# USB_OTG.net
KiCad netlist of a schematic drawn in Altium Designer
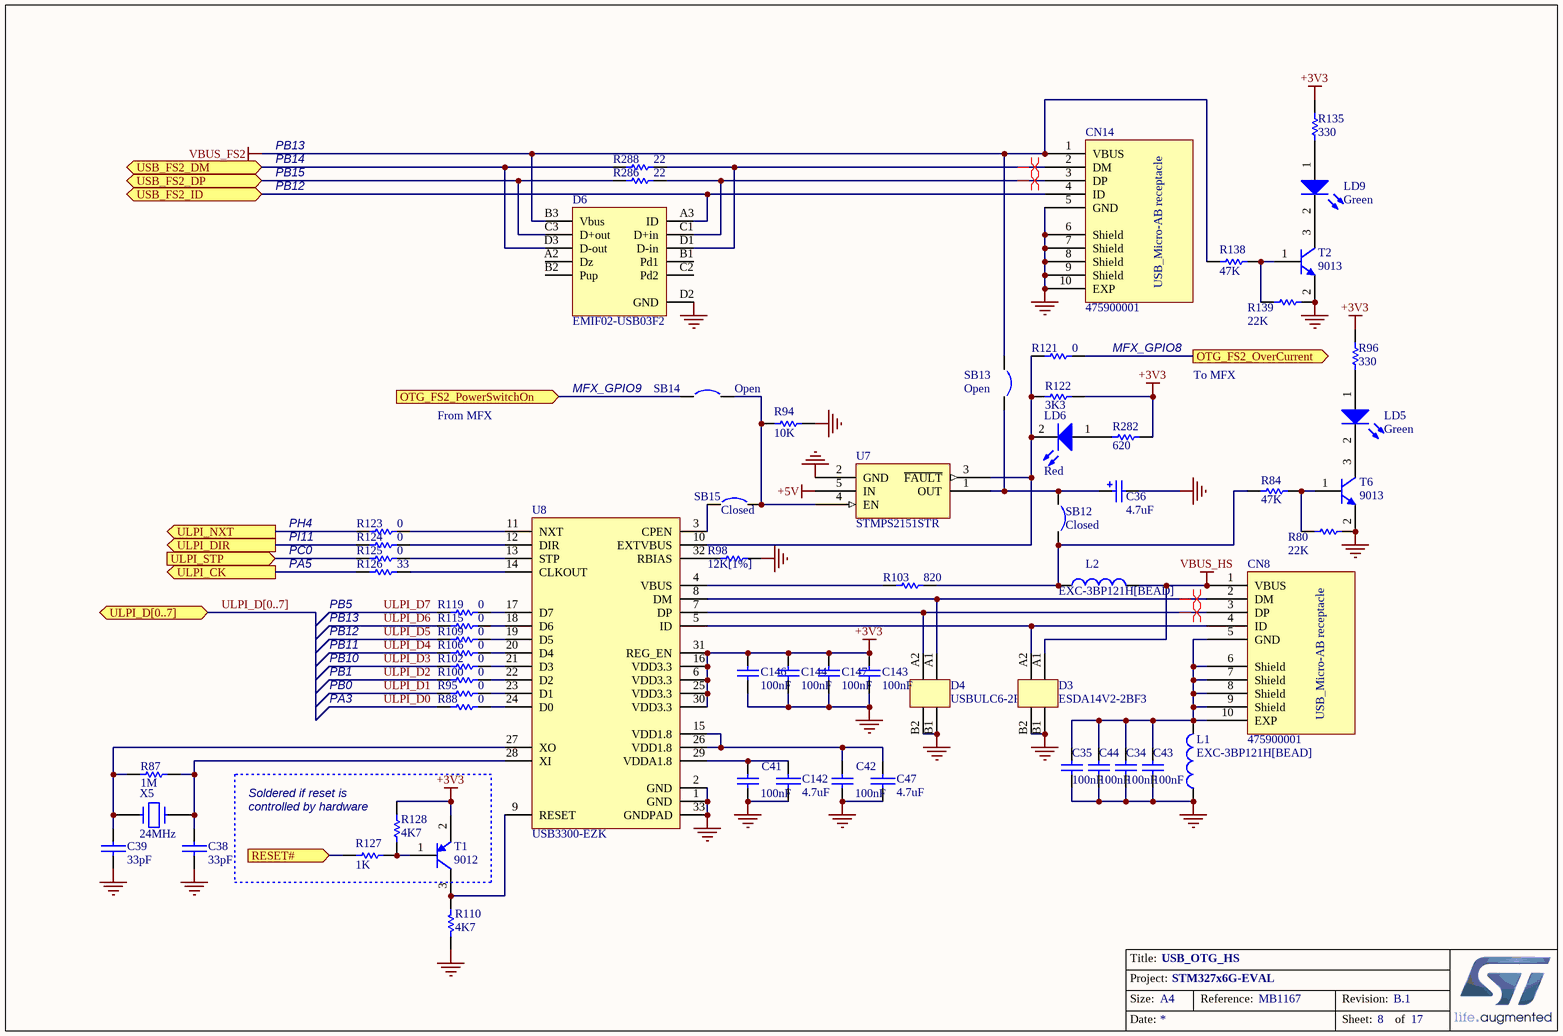
[diagram p0: USB_OTG.SchDoc]

(export (version "E")
  (design (tool "Eeschema 10.0.6"))
  (components
    (comp (ref "C34")
      (value "100nF")
      (footprint "0603C")
      (description "Capacitor")
      (fields (field (name "PUBLISHER") "Altium Limited"))
      (libsource (lib "Miscellaneous Devices") (part "Cap"))
    )
    (comp (ref "C35")
      (value "100nF")
      (footprint "0603C")
      (description "Capacitor")
      (fields (field (name "PUBLISHER") "Altium Limited"))
      (libsource (lib "Miscellaneous Devices") (part "Cap"))
    )
    (comp (ref "C36")
      (value "4.7uF")
      (footprint "TAN-A")
      (description "Polarized Capacitor (Radial)")
      (fields (field (name "PUBLISHER") "Altium Limited"))
      (libsource (lib "Miscellaneous Devices") (part "Cap Pol1"))
    )
    (comp (ref "C38")
      (value "33pF")
      (footprint "0603C")
      (description "Capacitor")
      (libsource (lib "") (part "CAP_1"))
    )
    (comp (ref "C39")
      (value "33pF")
      (footprint "0603C")
      (description "Capacitor")
      (libsource (lib "") (part "CAP_1"))
    )
    (comp (ref "C41")
      (value "100nF")
      (footprint "0603C")
      (description "Capacitor")
      (fields (field (name "PUBLISHER") "Altium Limited"))
      (libsource (lib "Miscellaneous Devices") (part "Cap"))
    )
    (comp (ref "C42")
      (value "100nF")
      (footprint "0603C")
      (description "Capacitor")
      (fields (field (name "PUBLISHER") "Altium Limited"))
      (libsource (lib "Miscellaneous Devices") (part "Cap"))
    )
    (comp (ref "C43")
      (value "100nF")
      (footprint "0603C")
      (description "Capacitor")
      (fields (field (name "PUBLISHER") "Altium Limited"))
      (libsource (lib "Miscellaneous Devices") (part "Cap"))
    )
    (comp (ref "C44")
      (value "100nF")
      (footprint "0603C")
      (description "Capacitor")
      (fields (field (name "PUBLISHER") "Altium Limited"))
      (libsource (lib "Miscellaneous Devices") (part "Cap"))
    )
    (comp (ref "C47")
      (value "4.7uF")
      (footprint "TAN-A")
      (description "Capacitor")
      (libsource (lib "*") (part "CAP"))
    )
    (comp (ref "C142")
      (value "4.7uF")
      (footprint "TAN-A")
      (description "Capacitor")
      (libsource (lib "*") (part "CAP"))
    )
    (comp (ref "C143")
      (value "100nF")
      (footprint "0603C")
      (description "Capacitor")
      (fields (field (name "PUBLISHER") "Altium Limited"))
      (libsource (lib "Miscellaneous Devices") (part "Cap"))
    )
    (comp (ref "C144")
      (value "100nF")
      (footprint "0603C")
      (description "Capacitor")
      (fields (field (name "PUBLISHER") "Altium Limited"))
      (libsource (lib "Miscellaneous Devices") (part "Cap"))
    )
    (comp (ref "C146")
      (value "100nF")
      (footprint "0603C")
      (description "Capacitor")
      (fields (field (name "PUBLISHER") "Altium Limited"))
      (libsource (lib "Miscellaneous Devices") (part "Cap"))
    )
    (comp (ref "C147")
      (value "100nF")
      (footprint "0603C")
      (description "Capacitor")
      (fields (field (name "PUBLISHER") "Altium Limited"))
      (libsource (lib "Miscellaneous Devices") (part "Cap"))
    )
    (comp (ref "CN8")
      (value "475900001")
      (footprint "MOLEX_47590001")
      (libsource (lib "mb1045") (part "475900001"))
    )
    (comp (ref "CN14")
      (value "475900001")
      (footprint "MOLEX_47590001")
      (libsource (lib "mb1045") (part "475900001"))
    )
    (comp (ref "D3")
      (value "ESDA14V2-2BF3")
      (footprint "BGA4_0R4_0R8X0R8")
      (libsource (lib "MB786") (part "ESDA14V2-2BF3"))
    )
    (comp (ref "D4")
      (value "USBULC6-2F3")
      (footprint "BGA4_0R4_1X1")
      (libsource (lib "MB786") (part "USBULC6-2F3"))
    )
    (comp (ref "D6")
      (value "EMIF02-USB03F2")
      (footprint "BGA11_0R5_1R57X2R07")
      (libsource (lib "mb1045") (part "EMIF02-USB03F2"))
    )
    (comp (ref "L1")
      (value "EXC-3BP121H[BEAD]")
      (footprint "0603L")
      (description "Inductor")
      (fields (field (name "PUBLISHER") "Altium Limited"))
      (libsource (lib "Miscellaneous Devices") (part "Inductor"))
    )
    (comp (ref "L2")
      (value "EXC-3BP121H[BEAD]")
      (footprint "0603L")
      (description "Inductor")
      (fields (field (name "PUBLISHER") "Altium Limited"))
      (libsource (lib "Miscellaneous Devices") (part "Inductor"))
    )
    (comp (ref "LD5")
      (value "Green")
      (footprint "0603D")
      (description "Typical RED, GREEN, YELLOW, AMBER GaAs LED")
      (fields (field (name "PUBLISHER") "Altium Limited"))
      (libsource (lib "Miscellaneous Devices") (part "LED2"))
    )
    (comp (ref "LD6")
      (value "Red")
      (footprint "0603D")
      (description "Typical RED, GREEN, YELLOW, AMBER GaAs LED")
      (fields (field (name "PUBLISHER") "Altium Limited"))
      (libsource (lib "Miscellaneous Devices") (part "LED2"))
    )
    (comp (ref "LD9")
      (value "Green")
      (footprint "0603D")
      (description "Typical RED, GREEN, YELLOW, AMBER GaAs LED")
      (fields (field (name "PUBLISHER") "Altium Limited"))
      (libsource (lib "Miscellaneous Devices") (part "LED2"))
    )
    (comp (ref "R80")
      (value "22K")
      (footprint "0603R")
      (description "Resistor")
      (fields (field (name "PUBLISHER") "Altium Limited"))
      (libsource (lib "Miscellaneous Devices") (part "res1"))
    )
    (comp (ref "R84")
      (value "47K")
      (footprint "0603R")
      (description "Resistor")
      (fields (field (name "PUBLISHER") "Altium Limited"))
      (libsource (lib "Miscellaneous Devices") (part "res1"))
    )
    (comp (ref "R87")
      (value "1M")
      (footprint "0603R")
      (description "Resistor")
      (fields (field (name "PUBLISHER") "Altium Limited"))
      (libsource (lib "Miscellaneous Devices") (part "Res1"))
    )
    (comp (ref "R88")
      (value "0")
      (footprint "0603R")
      (description "Resistor")
      (fields (field (name "PUBLISHER") "Altium Limited"))
      (libsource (lib "Miscellaneous Devices") (part "Res1"))
    )
    (comp (ref "R94")
      (value "10K")
      (footprint "0603R")
      (description "Resistor")
      (fields (field (name "PUBLISHER") "Altium Limited"))
      (libsource (lib "Miscellaneous Devices") (part "res1"))
    )
    (comp (ref "R95")
      (value "0")
      (footprint "0603R")
      (description "Resistor")
      (fields (field (name "PUBLISHER") "Altium Limited"))
      (libsource (lib "Miscellaneous Devices") (part "Res1"))
    )
    (comp (ref "R96")
      (value "330")
      (footprint "0603R")
      (description "Resistor")
      (fields (field (name "PUBLISHER") "Altium Limited"))
      (libsource (lib "Miscellaneous Devices") (part "res1"))
    )
    (comp (ref "R98")
      (value "12K[1%]")
      (footprint "0603R")
      (description "Resistor")
      (fields (field (name "PUBLISHER") "Altium Limited"))
      (libsource (lib "Miscellaneous Devices") (part "Res1"))
    )
    (comp (ref "R100")
      (value "0")
      (footprint "0603R")
      (description "Resistor")
      (fields (field (name "PUBLISHER") "Altium Limited"))
      (libsource (lib "Miscellaneous Devices") (part "Res1"))
    )
    (comp (ref "R102")
      (value "0")
      (footprint "0603R")
      (description "Resistor")
      (fields (field (name "PUBLISHER") "Altium Limited"))
      (libsource (lib "Miscellaneous Devices") (part "Res1"))
    )
    (comp (ref "R103")
      (value "820")
      (footprint "0603R")
      (description "Resistor")
      (fields (field (name "PUBLISHER") "Altium Limited"))
      (libsource (lib "Miscellaneous Devices") (part "res1"))
    )
    (comp (ref "R106")
      (value "0")
      (footprint "0603R")
      (description "Resistor")
      (fields (field (name "PUBLISHER") "Altium Limited"))
      (libsource (lib "Miscellaneous Devices") (part "Res1"))
    )
    (comp (ref "R109")
      (value "0")
      (footprint "0603R")
      (description "Resistor")
      (fields (field (name "PUBLISHER") "Altium Limited"))
      (libsource (lib "Miscellaneous Devices") (part "Res1"))
    )
    (comp (ref "R110")
      (value "4K7")
      (footprint "0603R")
      (description "Resistor")
      (fields (field (name "PUBLISHER") "Altium Limited"))
      (libsource (lib "*") (part "Res1"))
    )
    (comp (ref "R115")
      (value "0")
      (footprint "0603R")
      (description "Resistor")
      (fields (field (name "PUBLISHER") "Altium Limited"))
      (libsource (lib "Miscellaneous Devices") (part "Res1"))
    )
    (comp (ref "R119")
      (value "0")
      (footprint "0603R")
      (description "Resistor")
      (fields (field (name "PUBLISHER") "Altium Limited"))
      (libsource (lib "Miscellaneous Devices") (part "Res1"))
    )
    (comp (ref "R121")
      (value "0")
      (footprint "0603R")
      (description "Resistor")
      (fields (field (name "PUBLISHER") "Altium Limited"))
      (libsource (lib "Miscellaneous Devices") (part "Res1"))
    )
    (comp (ref "R122")
      (value "3K3")
      (footprint "0603R")
      (description "Resistor")
      (fields (field (name "PUBLISHER") "Altium Limited"))
      (libsource (lib "Miscellaneous Devices") (part "res1"))
    )
    (comp (ref "R123")
      (value "0")
      (footprint "0603R")
      (description "Resistor")
      (fields (field (name "PUBLISHER") "Altium Limited"))
      (libsource (lib "Miscellaneous Devices") (part "Res1"))
    )
    (comp (ref "R124")
      (value "0")
      (footprint "0603R")
      (description "Resistor")
      (fields (field (name "PUBLISHER") "Altium Limited"))
      (libsource (lib "Miscellaneous Devices") (part "Res1"))
    )
    (comp (ref "R125")
      (value "0")
      (footprint "0603R")
      (description "Resistor")
      (fields (field (name "PUBLISHER") "Altium Limited"))
      (libsource (lib "Miscellaneous Devices") (part "Res1"))
    )
    (comp (ref "R126")
      (value "33")
      (footprint "0603R")
      (description "Resistor")
      (fields (field (name "PUBLISHER") "Altium Limited"))
      (libsource (lib "Miscellaneous Devices") (part "Res1"))
    )
    (comp (ref "R127")
      (value "1K")
      (footprint "0603R")
      (description "Resistor")
      (fields (field (name "PUBLISHER") "Altium Limited"))
      (libsource (lib "Miscellaneous Devices") (part "Res1"))
    )
    (comp (ref "R128")
      (value "4K7")
      (footprint "0603R")
      (description "Resistor")
      (fields (field (name "PUBLISHER") "Altium Limited"))
      (libsource (lib "*") (part "Res1"))
    )
    (comp (ref "R135")
      (value "330")
      (footprint "0603R")
      (description "Resistor")
      (fields (field (name "PUBLISHER") "Altium Limited"))
      (libsource (lib "Miscellaneous Devices") (part "res1"))
    )
    (comp (ref "R138")
      (value "47K")
      (footprint "0603R")
      (description "Resistor")
      (fields (field (name "PUBLISHER") "Altium Limited"))
      (libsource (lib "Miscellaneous Devices") (part "res1"))
    )
    (comp (ref "R139")
      (value "22K")
      (footprint "0603R")
      (description "Resistor")
      (fields (field (name "PUBLISHER") "Altium Limited"))
      (libsource (lib "Miscellaneous Devices") (part "res1"))
    )
    (comp (ref "R282")
      (value "620")
      (footprint "0603R")
      (description "Resistor")
      (fields (field (name "PUBLISHER") "Altium Limited"))
      (libsource (lib "Miscellaneous Devices") (part "Res1"))
    )
    (comp (ref "R286")
      (value "22")
      (footprint "0603R")
      (description "Resistor")
      (fields (field (name "PUBLISHER") "Altium Limited"))
      (libsource (lib "Miscellaneous Devices") (part "Res1"))
    )
    (comp (ref "R288")
      (value "22")
      (footprint "0603R")
      (description "Resistor")
      (fields (field (name "PUBLISHER") "Altium Limited"))
      (libsource (lib "Miscellaneous Devices") (part "Res1"))
    )
    (comp (ref "SB12")
      (value "Closed")
      (footprint "SB_0603")
      (description "Circuit Breaker")
      (fields (field (name "PUBLISHER") "Altium Limited"))
      (libsource (lib "MB1167") (part "Circuit Breaker_close"))
    )
    (comp (ref "SB13")
      (value "Open")
      (footprint "SB_0603")
      (description "Circuit Breaker")
      (fields (field (name "PUBLISHER") "Altium Limited"))
      (libsource (lib "MB1167") (part "Circuit Breaker"))
    )
    (comp (ref "SB14")
      (value "Open")
      (footprint "SB_0603")
      (description "Circuit Breaker")
      (fields (field (name "PUBLISHER") "Altium Limited"))
      (libsource (lib "MB1167") (part "Circuit Breaker"))
    )
    (comp (ref "SB15")
      (value "Closed")
      (footprint "SB_0603")
      (description "Circuit Breaker")
      (fields (field (name "PUBLISHER") "Altium Limited"))
      (libsource (lib "MB1167") (part "Circuit Breaker_close"))
    )
    (comp (ref "T1")
      (value "9012")
      (footprint "SOT-23")
      (description "PNP Bipolar Transistor")
      (fields (field (name "PUBLISHER") "Altium Limited"))
      (libsource (lib "MB1167") (part "PNP"))
    )
    (comp (ref "T2")
      (value "9013")
      (footprint "SOT-23")
      (description "NPN Bipolar Transistor")
      (fields (field (name "PUBLISHER") "Altium Limited"))
      (libsource (lib "MB1167") (part "NPN"))
    )
    (comp (ref "T6")
      (value "9013")
      (footprint "SOT-23")
      (description "NPN Bipolar Transistor")
      (fields (field (name "PUBLISHER") "Altium Limited"))
      (libsource (lib "MB1167") (part "NPN"))
    )
    (comp (ref "U7")
      (value "STMPS2151STR")
      (footprint "SOT23-5")
      (libsource (lib "mb1045") (part "STMPS2141STR"))
    )
    (comp (ref "U8")
      (value "USB3300-EZK")
      (footprint "QFN32_0R5_5X5")
      (libsource (lib "MB1000_1") (part "USB3300-EZK"))
    )
    (comp (ref "X5")
      (value "24MHz")
      (footprint "XTAL1")
      (description "Crystal")
      (libsource (lib "*") (part "CRYSTAL"))
    )
  )
  (nets
    (net (code "1") (name "+3V3") (class "Default")
      (node (ref "C143") (pin "1") (pinfunction "1_1") (pintype "passive"))
      (node (ref "C144") (pin "1") (pinfunction "1_1") (pintype "passive"))
      (node (ref "C146") (pin "1") (pinfunction "1_1") (pintype "passive"))
      (node (ref "C147") (pin "1") (pinfunction "1_1") (pintype "passive"))
      (node (ref "R122") (pin "1") (pinfunction "1_1") (pintype "passive"))
      (node (ref "R128") (pin "1") (pinfunction "1_1") (pintype "passive"))
      (node (ref "R135") (pin "2") (pinfunction "2_2") (pintype "passive"))
      (node (ref "R282") (pin "2") (pinfunction "2_2") (pintype "passive"))
      (node (ref "R96") (pin "2") (pinfunction "2_2") (pintype "passive"))
      (node (ref "T1") (pin "2") (pinfunction "E_2") (pintype "passive"))
      (node (ref "U8") (pin "16") (pinfunction "VDD3.3_16") (pintype "passive"))
      (node (ref "U8") (pin "25") (pinfunction "VDD3.3_25") (pintype "passive"))
      (node (ref "U8") (pin "30") (pinfunction "VDD3.3_30") (pintype "passive"))
      (node (ref "U8") (pin "31") (pinfunction "REG_EN_31") (pintype "passive"))
      (node (ref "U8") (pin "6") (pinfunction "VDD3.3_6") (pintype "passive"))
    )
    (net (code "2") (name "+5V") (class "Default")
      (node (ref "U7") (pin "5") (pinfunction "IN_5") (pintype "passive"))
    )
    (net (code "3") (name "/OTG_FS2_OverCurrent") (class "Default")
      (node (ref "R121") (pin "1") (pinfunction "1_1") (pintype "passive"))
    )
    (net (code "4") (name "/OTG_FS2_PowerSwitchOn") (class "Default")
      (node (ref "SB14") (pin "1") (pinfunction "1_1") (pintype "passive"))
    )
    (net (code "5") (name "/RESET#") (class "Default")
      (node (ref "R127") (pin "2") (pinfunction "2_2") (pintype "passive"))
    )
    (net (code "6") (name "/ULPI_CK") (class "Default")
      (node (ref "R126") (pin "2") (pinfunction "2_2") (pintype "passive"))
    )
    (net (code "7") (name "/ULPI_D0") (class "Default")
      (node (ref "R88") (pin "2") (pinfunction "2_2") (pintype "passive"))
    )
    (net (code "8") (name "/ULPI_D1") (class "Default")
      (node (ref "R95") (pin "2") (pinfunction "2_2") (pintype "passive"))
    )
    (net (code "9") (name "/ULPI_D2") (class "Default")
      (node (ref "R100") (pin "2") (pinfunction "2_2") (pintype "passive"))
    )
    (net (code "10") (name "/ULPI_D3") (class "Default")
      (node (ref "R102") (pin "2") (pinfunction "2_2") (pintype "passive"))
    )
    (net (code "11") (name "/ULPI_D4") (class "Default")
      (node (ref "R106") (pin "2") (pinfunction "2_2") (pintype "passive"))
    )
    (net (code "12") (name "/ULPI_D5") (class "Default")
      (node (ref "R109") (pin "2") (pinfunction "2_2") (pintype "passive"))
    )
    (net (code "13") (name "/ULPI_D6") (class "Default")
      (node (ref "R115") (pin "2") (pinfunction "2_2") (pintype "passive"))
    )
    (net (code "14") (name "/ULPI_D7") (class "Default")
      (node (ref "R119") (pin "2") (pinfunction "2_2") (pintype "passive"))
    )
    (net (code "15") (name "/ULPI_DIR") (class "Default")
      (node (ref "R124") (pin "2") (pinfunction "2_2") (pintype "passive"))
    )
    (net (code "17") (name "/ULPI_NXT") (class "Default")
      (node (ref "R123") (pin "2") (pinfunction "2_2") (pintype "passive"))
    )
    (net (code "18") (name "/ULPI_STP") (class "Default")
      (node (ref "R125") (pin "2") (pinfunction "2_2") (pintype "passive"))
    )
    (net (code "19") (name "/USB_FS2_DM") (class "Default")
      (node (ref "D6") (pin "D3") (pinfunction "D-out_D3") (pintype "passive"))
      (node (ref "R288") (pin "2") (pinfunction "2_2") (pintype "passive"))
    )
    (net (code "20") (name "/USB_FS2_DP") (class "Default")
      (node (ref "D6") (pin "C3") (pinfunction "D+out_C3") (pintype "passive"))
      (node (ref "R286") (pin "2") (pinfunction "2_2") (pintype "passive"))
    )
    (net (code "21") (name "/USB_FS2_ID") (class "Default")
      (node (ref "CN14") (pin "4") (pinfunction "ID_4") (pintype "passive"))
      (node (ref "D6") (pin "A3") (pinfunction "ID_A3") (pintype "passive"))
    )
    (net (code "22") (name "GND") (class "Default")
      (node (ref "C142") (pin "2") (pinfunction "2_2") (pintype "passive"))
      (node (ref "C143") (pin "2") (pinfunction "2_2") (pintype "passive"))
      (node (ref "C144") (pin "2") (pinfunction "2_2") (pintype "passive"))
      (node (ref "C146") (pin "2") (pinfunction "2_2") (pintype "passive"))
      (node (ref "C147") (pin "2") (pinfunction "2_2") (pintype "passive"))
      (node (ref "C34") (pin "2") (pinfunction "2_2") (pintype "passive"))
      (node (ref "C35") (pin "2") (pinfunction "2_2") (pintype "passive"))
      (node (ref "C36") (pin "2") (pinfunction "2_2") (pintype "passive"))
      (node (ref "C38") (pin "2") (pinfunction "2_2") (pintype "passive"))
      (node (ref "C39") (pin "2") (pinfunction "2_2") (pintype "passive"))
      (node (ref "C41") (pin "2") (pinfunction "2_2") (pintype "passive"))
      (node (ref "C42") (pin "2") (pinfunction "2_2") (pintype "passive"))
      (node (ref "C43") (pin "2") (pinfunction "2_2") (pintype "passive"))
      (node (ref "C44") (pin "2") (pinfunction "2_2") (pintype "passive"))
      (node (ref "C47") (pin "2") (pinfunction "2_2") (pintype "passive"))
      (node (ref "CN14") (pin "10") (pinfunction "EXP_10") (pintype "passive"))
      (node (ref "CN14") (pin "5") (pinfunction "GND_5") (pintype "passive"))
      (node (ref "CN14") (pin "6") (pinfunction "Shield_6") (pintype "passive"))
      (node (ref "CN14") (pin "7") (pinfunction "Shield_7") (pintype "passive"))
      (node (ref "CN14") (pin "8") (pinfunction "Shield_8") (pintype "passive"))
      (node (ref "CN14") (pin "9") (pinfunction "Shield_9") (pintype "passive"))
      (node (ref "D3") (pin "B1") (pintype "passive"))
      (node (ref "D3") (pin "B2") (pintype "passive"))
      (node (ref "D4") (pin "B1") (pintype "passive"))
      (node (ref "D4") (pin "B2") (pintype "passive"))
      (node (ref "D6") (pin "D2") (pinfunction "GND_D2") (pintype "passive"))
      (node (ref "L1") (pin "1") (pinfunction "1_1") (pintype "passive"))
      (node (ref "R110") (pin "1") (pinfunction "1_1") (pintype "passive"))
      (node (ref "R139") (pin "1") (pinfunction "1_1") (pintype "passive"))
      (node (ref "R80") (pin "1") (pinfunction "1_1") (pintype "passive"))
      (node (ref "R94") (pin "1") (pinfunction "1_1") (pintype "passive"))
      (node (ref "R98") (pin "1") (pinfunction "1_1") (pintype "passive"))
      (node (ref "T2") (pin "2") (pinfunction "E_2") (pintype "passive"))
      (node (ref "T6") (pin "2") (pinfunction "E_2") (pintype "passive"))
      (node (ref "U7") (pin "2") (pinfunction "GND_2") (pintype "passive"))
      (node (ref "U8") (pin "1") (pinfunction "GND_1") (pintype "passive"))
      (node (ref "U8") (pin "2") (pinfunction "GND_2") (pintype "passive"))
      (node (ref "U8") (pin "33") (pinfunction "GNDPAD_33") (pintype "passive"))
    )
    (net (code "23") (name "Net-(C42-Pad1)") (class "Default")
      (node (ref "C42") (pin "1") (pinfunction "1_1") (pintype "passive"))
      (node (ref "C47") (pin "1") (pinfunction "1_1") (pintype "passive"))
      (node (ref "U8") (pin "15") (pinfunction "VDD1.8_15") (pintype "passive"))
      (node (ref "U8") (pin "26") (pinfunction "VDD1.8_26") (pintype "passive"))
    )
    (net (code "24") (name "Net-(CN8-DM)") (class "Default")
      (node (ref "CN8") (pin "2") (pinfunction "DM_2") (pintype "passive"))
      (node (ref "D4") (pin "A1") (pintype "passive"))
      (node (ref "U8") (pin "8") (pinfunction "DM_8") (pintype "passive"))
    )
    (net (code "25") (name "Net-(CN8-DP)") (class "Default")
      (node (ref "CN8") (pin "3") (pinfunction "DP_3") (pintype "passive"))
      (node (ref "D4") (pin "A2") (pintype "passive"))
      (node (ref "U8") (pin "7") (pinfunction "DP_7") (pintype "passive"))
    )
    (net (code "26") (name "Net-(CN8-EXP)") (class "Default")
      (node (ref "C34") (pin "1") (pinfunction "1_1") (pintype "passive"))
      (node (ref "C35") (pin "1") (pinfunction "1_1") (pintype "passive"))
      (node (ref "C43") (pin "1") (pinfunction "1_1") (pintype "passive"))
      (node (ref "C44") (pin "1") (pinfunction "1_1") (pintype "passive"))
      (node (ref "CN8") (pin "10") (pinfunction "EXP_10") (pintype "passive"))
      (node (ref "CN8") (pin "5") (pinfunction "GND_5") (pintype "passive"))
      (node (ref "CN8") (pin "6") (pinfunction "Shield_6") (pintype "passive"))
      (node (ref "CN8") (pin "7") (pinfunction "Shield_7") (pintype "passive"))
      (node (ref "CN8") (pin "8") (pinfunction "Shield_8") (pintype "passive"))
      (node (ref "CN8") (pin "9") (pinfunction "Shield_9") (pintype "passive"))
      (node (ref "L1") (pin "2") (pinfunction "2_2") (pintype "passive"))
    )
    (net (code "27") (name "Net-(CN8-ID)") (class "Default")
      (node (ref "CN8") (pin "4") (pinfunction "ID_4") (pintype "passive"))
      (node (ref "D3") (pin "A2") (pintype "passive"))
      (node (ref "U8") (pin "5") (pinfunction "ID_5") (pintype "passive"))
    )
    (net (code "28") (name "Net-(CN14-DM)") (class "Default")
      (node (ref "CN14") (pin "2") (pinfunction "DM_2") (pintype "passive"))
      (node (ref "D6") (pin "D1") (pinfunction "D-in_D1") (pintype "passive"))
      (node (ref "R288") (pin "1") (pinfunction "1_1") (pintype "passive"))
    )
    (net (code "29") (name "Net-(CN14-DP)") (class "Default")
      (node (ref "CN14") (pin "3") (pinfunction "DP_3") (pintype "passive"))
      (node (ref "D6") (pin "C1") (pinfunction "D+in_C1") (pintype "passive"))
      (node (ref "R286") (pin "1") (pinfunction "1_1") (pintype "passive"))
    )
    (net (code "30") (name "Net-(L2-Pad1)") (class "Default")
      (node (ref "L2") (pin "1") (pinfunction "1_1") (pintype "passive"))
      (node (ref "R103") (pin "2") (pinfunction "2_2") (pintype "passive"))
      (node (ref "R84") (pin "2") (pinfunction "2_2") (pintype "passive"))
      (node (ref "SB12") (pin "2") (pinfunction "2_2") (pintype "passive"))
    )
    (net (code "31") (name "Net-(LD5-A)") (class "Default")
      (node (ref "LD5") (pin "1") (pinfunction "A_1") (pintype "passive"))
      (node (ref "R96") (pin "1") (pinfunction "1_1") (pintype "passive"))
    )
    (net (code "32") (name "Net-(LD5-K)") (class "Default")
      (node (ref "LD5") (pin "2") (pinfunction "K_2") (pintype "passive"))
      (node (ref "T6") (pin "3") (pinfunction "C_3") (pintype "passive"))
    )
    (net (code "33") (name "Net-(LD6-A)") (class "Default")
      (node (ref "LD6") (pin "1") (pinfunction "A_1") (pintype "passive"))
      (node (ref "R282") (pin "1") (pinfunction "1_1") (pintype "passive"))
    )
    (net (code "34") (name "Net-(LD6-K)") (class "Default")
      (node (ref "LD6") (pin "2") (pinfunction "K_2") (pintype "passive"))
      (node (ref "R121") (pin "2") (pinfunction "2_2") (pintype "passive"))
      (node (ref "R122") (pin "2") (pinfunction "2_2") (pintype "passive"))
      (node (ref "U7") (pin "3") (pinfunction "~{FAULT}_3") (pintype "output"))
      (node (ref "U8") (pin "10") (pinfunction "EXTVBUS_10") (pintype "passive"))
    )
    (net (code "35") (name "Net-(LD9-A)") (class "Default")
      (node (ref "LD9") (pin "1") (pinfunction "A_1") (pintype "passive"))
      (node (ref "R135") (pin "1") (pinfunction "1_1") (pintype "passive"))
    )
    (net (code "36") (name "Net-(LD9-K)") (class "Default")
      (node (ref "LD9") (pin "2") (pinfunction "K_2") (pintype "passive"))
      (node (ref "T2") (pin "3") (pinfunction "C_3") (pintype "passive"))
    )
    (net (code "37") (name "Net-(T1-B)") (class "Default")
      (node (ref "R127") (pin "1") (pinfunction "1_1") (pintype "passive"))
      (node (ref "R128") (pin "2") (pinfunction "2_2") (pintype "passive"))
      (node (ref "T1") (pin "1") (pinfunction "B_1") (pintype "passive"))
    )
    (net (code "38") (name "Net-(T1-C)") (class "Default")
      (node (ref "R110") (pin "2") (pinfunction "2_2") (pintype "passive"))
      (node (ref "T1") (pin "3") (pinfunction "C_3") (pintype "passive"))
      (node (ref "U8") (pin "9") (pinfunction "RESET_9") (pintype "passive"))
    )
    (net (code "39") (name "Net-(T2-B)") (class "Default")
      (node (ref "R138") (pin "2") (pinfunction "2_2") (pintype "passive"))
      (node (ref "R139") (pin "2") (pinfunction "2_2") (pintype "passive"))
      (node (ref "T2") (pin "1") (pinfunction "B_1") (pintype "passive"))
    )
    (net (code "40") (name "Net-(T6-B)") (class "Default")
      (node (ref "R80") (pin "2") (pinfunction "2_2") (pintype "passive"))
      (node (ref "R84") (pin "1") (pinfunction "1_1") (pintype "passive"))
      (node (ref "T6") (pin "1") (pinfunction "B_1") (pintype "passive"))
    )
    (net (code "41") (name "Net-(U7-EN)") (class "Default")
      (node (ref "R94") (pin "2") (pinfunction "2_2") (pintype "passive"))
      (node (ref "SB14") (pin "2") (pinfunction "2_2") (pintype "passive"))
      (node (ref "SB15") (pin "2") (pinfunction "2_2") (pintype "passive"))
      (node (ref "U7") (pin "4") (pinfunction "EN_4") (pintype "input"))
    )
    (net (code "42") (name "Net-(U7-OUT)") (class "Default")
      (node (ref "C36") (pin "1") (pinfunction "1_1") (pintype "passive"))
      (node (ref "SB12") (pin "1") (pinfunction "1_1") (pintype "passive"))
      (node (ref "SB13") (pin "2") (pinfunction "2_2") (pintype "passive"))
      (node (ref "U7") (pin "1") (pinfunction "OUT_1") (pintype "passive"))
    )
    (net (code "43") (name "Net-(U8-CLKOUT)") (class "Default")
      (node (ref "R126") (pin "1") (pinfunction "1_1") (pintype "passive"))
      (node (ref "U8") (pin "14") (pinfunction "CLKOUT_14") (pintype "passive"))
    )
    (net (code "44") (name "Net-(U8-CPEN)") (class "Default")
      (node (ref "SB15") (pin "1") (pinfunction "1_1") (pintype "passive"))
      (node (ref "U8") (pin "3") (pinfunction "CPEN_3") (pintype "passive"))
    )
    (net (code "45") (name "Net-(U8-D0)") (class "Default")
      (node (ref "R88") (pin "1") (pinfunction "1_1") (pintype "passive"))
      (node (ref "U8") (pin "24") (pinfunction "D0_24") (pintype "passive"))
    )
    (net (code "46") (name "Net-(U8-D1)") (class "Default")
      (node (ref "R95") (pin "1") (pinfunction "1_1") (pintype "passive"))
      (node (ref "U8") (pin "23") (pinfunction "D1_23") (pintype "passive"))
    )
    (net (code "47") (name "Net-(U8-D2)") (class "Default")
      (node (ref "R100") (pin "1") (pinfunction "1_1") (pintype "passive"))
      (node (ref "U8") (pin "22") (pinfunction "D2_22") (pintype "passive"))
    )
    (net (code "48") (name "Net-(U8-D3)") (class "Default")
      (node (ref "R102") (pin "1") (pinfunction "1_1") (pintype "passive"))
      (node (ref "U8") (pin "21") (pinfunction "D3_21") (pintype "passive"))
    )
    (net (code "49") (name "Net-(U8-D4)") (class "Default")
      (node (ref "R106") (pin "1") (pinfunction "1_1") (pintype "passive"))
      (node (ref "U8") (pin "20") (pinfunction "D4_20") (pintype "passive"))
    )
    (net (code "50") (name "Net-(U8-D5)") (class "Default")
      (node (ref "R109") (pin "1") (pinfunction "1_1") (pintype "passive"))
      (node (ref "U8") (pin "19") (pinfunction "D5_19") (pintype "passive"))
    )
    (net (code "51") (name "Net-(U8-D6)") (class "Default")
      (node (ref "R115") (pin "1") (pinfunction "1_1") (pintype "passive"))
      (node (ref "U8") (pin "18") (pinfunction "D6_18") (pintype "passive"))
    )
    (net (code "52") (name "Net-(U8-D7)") (class "Default")
      (node (ref "R119") (pin "1") (pinfunction "1_1") (pintype "passive"))
      (node (ref "U8") (pin "17") (pinfunction "D7_17") (pintype "passive"))
    )
    (net (code "53") (name "Net-(U8-DIR)") (class "Default")
      (node (ref "R124") (pin "1") (pinfunction "1_1") (pintype "passive"))
      (node (ref "U8") (pin "12") (pinfunction "DIR_12") (pintype "passive"))
    )
    (net (code "54") (name "Net-(U8-NXT)") (class "Default")
      (node (ref "R123") (pin "1") (pinfunction "1_1") (pintype "passive"))
      (node (ref "U8") (pin "11") (pinfunction "NXT_11") (pintype "passive"))
    )
    (net (code "55") (name "Net-(U8-RBIAS)") (class "Default")
      (node (ref "R98") (pin "2") (pinfunction "2_2") (pintype "passive"))
      (node (ref "U8") (pin "32") (pinfunction "RBIAS_32") (pintype "passive"))
    )
    (net (code "56") (name "Net-(U8-STP)") (class "Default")
      (node (ref "R125") (pin "1") (pinfunction "1_1") (pintype "passive"))
      (node (ref "U8") (pin "13") (pinfunction "STP_13") (pintype "passive"))
    )
    (net (code "57") (name "Net-(U8-VBUS)") (class "Default")
      (node (ref "R103") (pin "1") (pinfunction "1_1") (pintype "passive"))
      (node (ref "U8") (pin "4") (pinfunction "VBUS_4") (pintype "passive"))
    )
    (net (code "58") (name "Net-(U8-VDDA1.8)") (class "Default")
      (node (ref "C142") (pin "1") (pinfunction "1_1") (pintype "passive"))
      (node (ref "C41") (pin "1") (pinfunction "1_1") (pintype "passive"))
      (node (ref "U8") (pin "29") (pinfunction "VDDA1.8_29") (pintype "passive"))
    )
    (net (code "59") (name "Net-(U8-XI)") (class "Default")
      (node (ref "C38") (pin "1") (pinfunction "1_1") (pintype "passive"))
      (node (ref "R87") (pin "2") (pinfunction "2_2") (pintype "passive"))
      (node (ref "U8") (pin "28") (pinfunction "XI_28") (pintype "passive"))
      (node (ref "X5") (pin "1") (pinfunction "1_1") (pintype "passive"))
    )
    (net (code "60") (name "Net-(U8-XO)") (class "Default")
      (node (ref "C39") (pin "1") (pinfunction "1_1") (pintype "passive"))
      (node (ref "R87") (pin "1") (pinfunction "1_1") (pintype "passive"))
      (node (ref "U8") (pin "27") (pinfunction "XO_27") (pintype "passive"))
      (node (ref "X5") (pin "2") (pinfunction "2_2") (pintype "passive"))
    )
    (net (code "61") (name "VBUS_FS2") (class "Default")
      (node (ref "CN14") (pin "1") (pinfunction "VBUS_1") (pintype "passive"))
      (node (ref "D6") (pin "B3") (pinfunction "Vbus_B3") (pintype "passive"))
      (node (ref "R138") (pin "1") (pinfunction "1_1") (pintype "passive"))
      (node (ref "SB13") (pin "1") (pinfunction "1_1") (pintype "passive"))
    )
    (net (code "62") (name "VBUS_HS") (class "Default")
      (node (ref "CN8") (pin "1") (pinfunction "VBUS_1") (pintype "passive"))
      (node (ref "D3") (pin "A1") (pintype "passive"))
      (node (ref "L2") (pin "2") (pinfunction "2_2") (pintype "passive"))
    )
    (net (code "63") (name "unconnected-(D6-Dz-PadA2)") (class "Default")
      (node (ref "D6") (pin "A2") (pinfunction "Dz_A2") (pintype "passive"))
    )
    (net (code "64") (name "unconnected-(D6-Pd1-PadB1)") (class "Default")
      (node (ref "D6") (pin "B1") (pinfunction "Pd1_B1") (pintype "passive"))
    )
    (net (code "65") (name "unconnected-(D6-Pd2-PadC2)") (class "Default")
      (node (ref "D6") (pin "C2") (pinfunction "Pd2_C2") (pintype "passive"))
    )
    (net (code "66") (name "unconnected-(D6-Pup-PadB2)") (class "Default")
      (node (ref "D6") (pin "B2") (pinfunction "Pup_B2") (pintype "passive"))
    )
  )
)
